# MAIN.net
KiCad netlist of a schematic drawn in Altium Designer
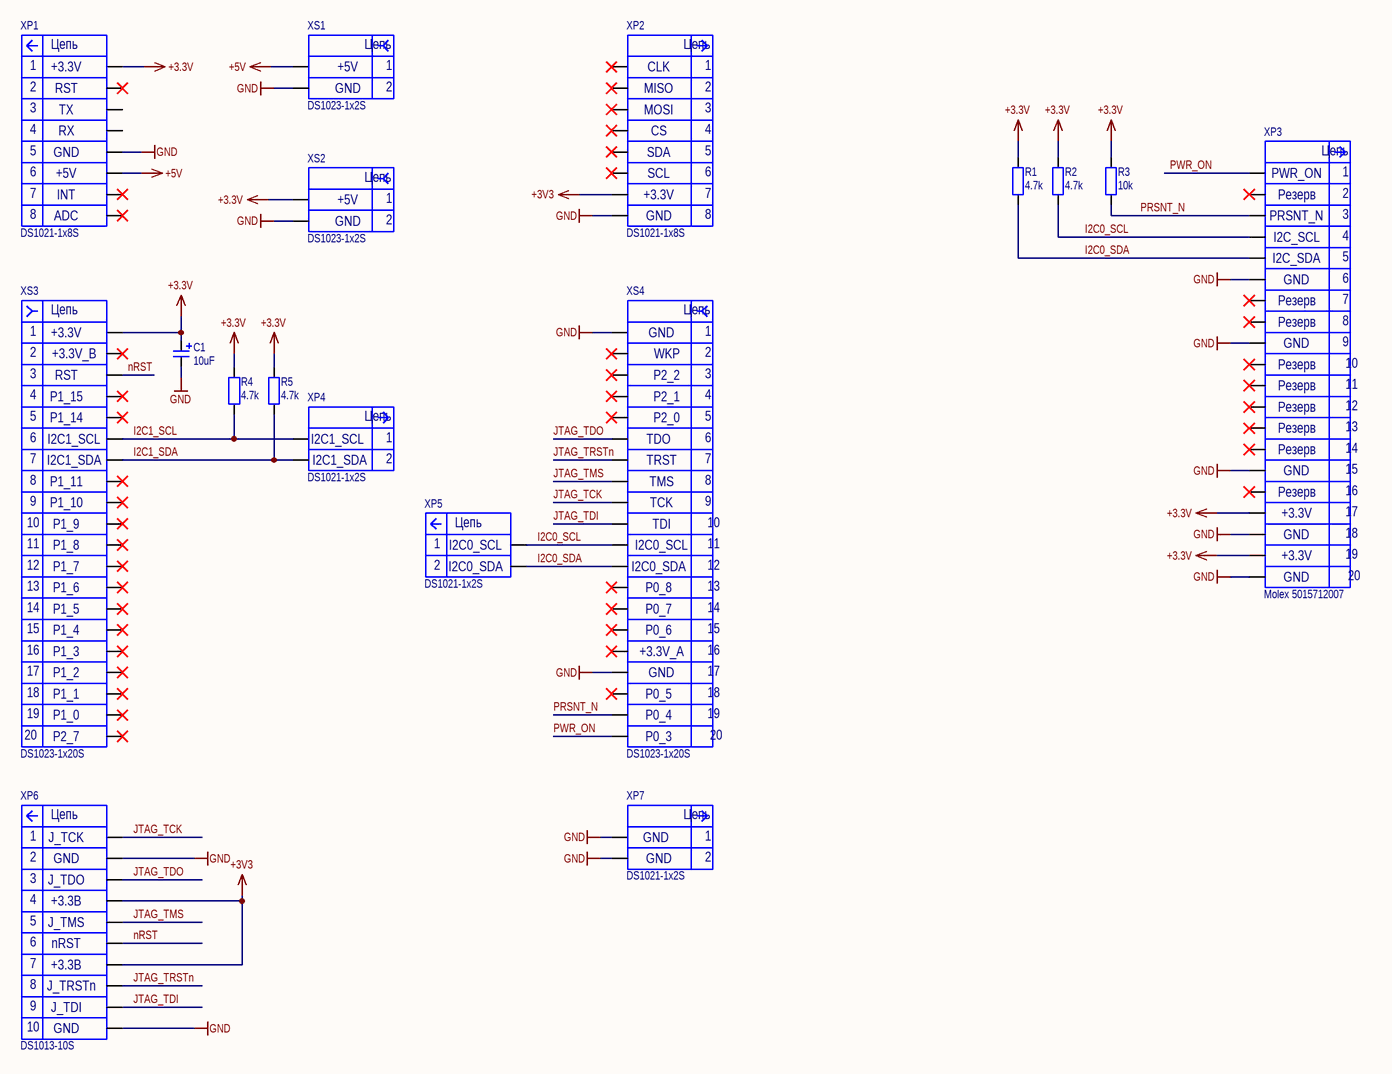
[diagram p0: MAIN.SchDoc]

(export (version "E")
  (design (tool "Eeschema 10.0.6"))
  (components
    (comp (ref "C1")
      (value "10uF")
      (footprint "CAP ALSMD ELEC 4.3MM H5.4MM")
      (description "Конденсатор К50-97 – 25В – 10мкФ (±20) % – ЕВАЯ.673541.054ТУ")
      (fields
        (field (name "MANUFACTURER PART NUMBER") "К50-97 – 25В – 10мкФ (±20) % – ЕВАЯ.673541.054ТУ")
        (field (name "TOLERANCE") "± 20%")
      )
      (libsource (lib "ComponentsDb") (part "Capacitor_Polar"))
    )
    (comp (ref "R1")
      (value "4.7k")
      (footprint "RES 0603_1608")
      (description "Резистор 0603-0,1Вт-4.7кОм ± 1%")
      (fields (field (name "MANUFACTURER PART NUMBER") "RC0603FR-074K7L") (field (name "TOLERANCE") "± 1%"))
      (libsource (lib "ComponentsDb") (part "Resistor_b"))
    )
    (comp (ref "R2")
      (value "4.7k")
      (footprint "RES 0603_1608")
      (description "Резистор 0603-0,1Вт-4.7кОм ± 1%")
      (fields (field (name "MANUFACTURER PART NUMBER") "RC0603FR-074K7L") (field (name "TOLERANCE") "± 1%"))
      (libsource (lib "ComponentsDb") (part "Resistor_b"))
    )
    (comp (ref "R3")
      (value "10k")
      (footprint "RES 0603_1608")
      (description "Резистор 0603-0,1Вт-10кОм ± 1%")
      (fields (field (name "MANUFACTURER PART NUMBER") "RC0603FR-0710KL") (field (name "TOLERANCE") "± 1%"))
      (libsource (lib "ComponentsDb") (part "Resistor_b"))
    )
    (comp (ref "R4")
      (value "4.7k")
      (footprint "RES 0603_1608")
      (description "Резистор 0603-0,1Вт-4.7кОм ± 1%")
      (fields (field (name "MANUFACTURER PART NUMBER") "RC0603FR-074K7L") (field (name "TOLERANCE") "± 1%"))
      (libsource (lib "ComponentsDb") (part "Resistor_b"))
    )
    (comp (ref "R5")
      (value "4.7k")
      (footprint "RES 0603_1608")
      (description "Резистор 0603-0,1Вт-4.7кОм ± 1%")
      (fields (field (name "MANUFACTURER PART NUMBER") "RC0603FR-074K7L") (field (name "TOLERANCE") "± 1%"))
      (libsource (lib "ComponentsDb") (part "Resistor_b"))
    )
    (comp (ref "XP1")
      (value "DS1021-1x8S")
      (footprint "DS1021-1x8S")
      (description "Соединитель DS1021-1x8S")
      (fields
        (field (name "NET_8") "ADC")
        (field (name "NET_7") "INT")
        (field (name "NET_6") "+5V")
        (field (name "NET_5") "GND")
        (field (name "NET_4") "RX")
        (field (name "NET_3") "TX")
        (field (name "NET_2") "RST")
        (field (name "NET_1") "+3.3V")
        (field (name "MANUFACTURER") "Connfly")
      )
      (libsource (lib "ComponentsDb") (part "Plug_8pin"))
    )
    (comp (ref "XP2")
      (value "DS1021-1x8S")
      (footprint "DS1021-1x8S")
      (description "Соединитель DS1021-1x8S")
      (fields
        (field (name "NET_8") "GND")
        (field (name "NET_7") "+3.3V")
        (field (name "NET_6") "SCL")
        (field (name "NET_5") "SDA")
        (field (name "NET_4") "CS")
        (field (name "NET_3") "MOSI")
        (field (name "NET_2") "MISO")
        (field (name "NET_1") "CLK")
        (field (name "MANUFACTURER") "Connfly")
      )
      (libsource (lib "ComponentsDb") (part "Plug_8pin"))
    )
    (comp (ref "XP3")
      (value "Molex 5015712007")
      (footprint "Molex 5015712007")
      (description "Соединитель Molex 5015712007")
      (fields
        (field (name "NET_20") "GND")
        (field (name "NET_19") "+3.3V")
        (field (name "NET_18") "GND")
        (field (name "NET_17") "+3.3V")
        (field (name "NET_16") "Резерв")
        (field (name "NET_15") "GND")
        (field (name "NET_14") "Резерв")
        (field (name "NET_13") "Резерв")
        (field (name "NET_12") "Резерв")
        (field (name "NET_11") "Резерв")
        (field (name "NET_10") "Резерв")
        (field (name "NET_9") "GND")
        (field (name "NET_8") "Резерв")
        (field (name "NET_7") "Резерв")
        (field (name "NET_6") "GND")
        (field (name "NET_5") "I2C_SDA")
        (field (name "NET_4") "I2C_SCL")
        (field (name "NET_3") "PRSNT_N")
        (field (name "NET_2") "Резерв")
        (field (name "NET_1") "PWR_ON")
        (field (name "MANUFACTURER") "Molex")
      )
      (libsource (lib "ComponentsDb") (part "Plug_20pin"))
    )
    (comp (ref "XP4")
      (value "DS1021-1x2S")
      (footprint "DS1021-1x2S")
      (description "Соединитель DS1021-1x2S")
      (fields
        (field (name "NET_2") "I2C1_SDA")
        (field (name "NET_1") "I2C1_SCL")
        (field (name "MANUFACTURER") "Connfly")
      )
      (libsource (lib "ComponentsDb") (part "Plug_2pin"))
    )
    (comp (ref "XP5")
      (value "DS1021-1x2S")
      (footprint "DS1021-1x2S")
      (description "Соединитель DS1021-1x2S")
      (fields
        (field (name "NET_2") "I2C0_SDA")
        (field (name "NET_1") "I2C0_SCL")
        (field (name "MANUFACTURER") "Connfly")
      )
      (libsource (lib "ComponentsDb") (part "Plug_2pin"))
    )
    (comp (ref "XP6")
      (value "DS1013-10S")
      (footprint "DS1013-10S")
      (description "Соединитель DS1013-10S")
      (fields
        (field (name "MANUFACTURER") "Connfly")
        (field (name "NET_10") "GND")
        (field (name "NET_9") "J_TDI")
        (field (name "NET_8") "J_TRSTn")
        (field (name "NET_7") "+3.3В")
        (field (name "NET_6") "nRST")
        (field (name "NET_5") "J_TMS")
        (field (name "NET_4") "+3.3В")
        (field (name "NET_3") "J_TDO")
        (field (name "NET_2") "GND")
        (field (name "NET_1") "J_TCK")
      )
      (libsource (lib "ComponentsDb") (part "Plug_10pin"))
    )
    (comp (ref "XP7")
      (value "DS1021-1x2S")
      (footprint "DS1021-1x2S")
      (description "Соединитель DS1021-1x2S")
      (fields
        (field (name "NET_2") "GND")
        (field (name "NET_1") "GND")
        (field (name "MANUFACTURER") "Connfly")
      )
      (libsource (lib "ComponentsDb") (part "Plug_2pin"))
    )
    (comp (ref "XS1")
      (value "DS1023-1x2S")
      (footprint "DS1023-1x2S")
      (description "Соединитель DS1023-1x2S")
      (fields
        (field (name "NET_2") "GND")
        (field (name "NET_1") "+5V")
        (field (name "MANUFACTURER") "Connfly")
      )
      (libsource (lib "ComponentsDb") (part "Socket_2pin"))
    )
    (comp (ref "XS2")
      (value "DS1023-1x2S")
      (footprint "DS1023-1x2S")
      (description "Соединитель DS1023-1x2S")
      (fields
        (field (name "NET_2") "GND")
        (field (name "NET_1") "+5V")
        (field (name "MANUFACTURER") "Connfly")
      )
      (libsource (lib "") (part "Socket_2pin_1"))
    )
    (comp (ref "XS3")
      (value "DS1023-1x20S")
      (footprint "DS1023-1x20S")
      (description "Соединитель DS1023-1x20S")
      (fields
        (field (name "NET_20") "P2_7")
        (field (name "NET_19") "P1_0")
        (field (name "NET_18") "P1_1")
        (field (name "NET_17") "P1_2")
        (field (name "NET_16") "P1_3")
        (field (name "NET_15") "P1_4")
        (field (name "NET_14") "P1_5")
        (field (name "NET_13") "P1_6")
        (field (name "NET_12") "P1_7")
        (field (name "NET_11") "P1_8")
        (field (name "NET_10") "P1_9")
        (field (name "NET_9") "P1_10")
        (field (name "NET_8") "P1_11")
        (field (name "NET_7") "I2C1_SDA")
        (field (name "NET_6") "I2C1_SCL")
        (field (name "NET_5") "P1_14")
        (field (name "NET_4") "P1_15")
        (field (name "NET_3") "RST")
        (field (name "NET_2") "+3.3V_B")
        (field (name "NET_1") "+3.3V")
        (field (name "MANUFACTURER") "Connfly")
      )
      (libsource (lib "ComponentsDb") (part "Socket_20pin"))
    )
    (comp (ref "XS4")
      (value "DS1023-1x20S")
      (footprint "DS1023-1x20S")
      (description "Соединитель DS1023-1x20S")
      (fields
        (field (name "NET_20") "P0_3")
        (field (name "NET_19") "P0_4")
        (field (name "NET_18") "P0_5")
        (field (name "NET_17") "GND")
        (field (name "NET_16") "+3.3V_A")
        (field (name "NET_15") "P0_6")
        (field (name "NET_14") "P0_7")
        (field (name "NET_13") "P0_8")
        (field (name "NET_12") "I2C0_SDA")
        (field (name "NET_11") "I2C0_SCL")
        (field (name "NET_10") "TDI")
        (field (name "NET_9") "TCK")
        (field (name "NET_8") "TMS")
        (field (name "NET_7") "TRST")
        (field (name "NET_6") "TDO")
        (field (name "NET_5") "P2_0")
        (field (name "NET_4") "P2_1")
        (field (name "NET_3") "P2_2")
        (field (name "NET_2") "WKP")
        (field (name "NET_1") "GND")
        (field (name "MANUFACTURER") "Connfly")
      )
      (libsource (lib "ComponentsDb") (part "Socket_20pin"))
    )
  )
  (nets
    (net (code "1") (name "+3.3V") (class "Default")
      (node (ref "C1") (pin "1") (pinfunction "P_1") (pintype "passive"))
      (node (ref "R1") (pin "2") (pinfunction "2_2") (pintype "passive"))
      (node (ref "R2") (pin "2") (pinfunction "2_2") (pintype "passive"))
      (node (ref "R3") (pin "2") (pinfunction "2_2") (pintype "passive"))
      (node (ref "R4") (pin "2") (pinfunction "2_2") (pintype "passive"))
      (node (ref "R5") (pin "2") (pinfunction "2_2") (pintype "passive"))
      (node (ref "XP1") (pin "1") (pinfunction "1_1") (pintype "passive"))
      (node (ref "XP3") (pin "17") (pinfunction "17_17") (pintype "passive"))
      (node (ref "XP3") (pin "19") (pinfunction "19_19") (pintype "passive"))
      (node (ref "XS2") (pin "1") (pinfunction "1_1") (pintype "passive"))
      (node (ref "XS3") (pin "1") (pinfunction "1_1") (pintype "passive"))
    )
    (net (code "2") (name "+3V3") (class "Default")
      (node (ref "XP2") (pin "7") (pinfunction "7_7") (pintype "passive"))
      (node (ref "XP6") (pin "4") (pinfunction "4_4") (pintype "passive"))
      (node (ref "XP6") (pin "7") (pinfunction "7_7") (pintype "passive"))
    )
    (net (code "3") (name "+5V") (class "Default")
      (node (ref "XP1") (pin "6") (pinfunction "6_6") (pintype "passive"))
      (node (ref "XS1") (pin "1") (pinfunction "1_1") (pintype "passive"))
    )
    (net (code "4") (name "/I2C0_SCL") (class "Default")
      (node (ref "R2") (pin "1") (pinfunction "1_1") (pintype "passive"))
      (node (ref "XP3") (pin "4") (pinfunction "4_4") (pintype "passive"))
      (node (ref "XP5") (pin "1") (pinfunction "1_1") (pintype "passive"))
      (node (ref "XS4") (pin "11") (pinfunction "11_11") (pintype "passive"))
    )
    (net (code "5") (name "/I2C0_SDA") (class "Default")
      (node (ref "R1") (pin "1") (pinfunction "1_1") (pintype "passive"))
      (node (ref "XP3") (pin "5") (pinfunction "5_5") (pintype "passive"))
      (node (ref "XP5") (pin "2") (pinfunction "2_2") (pintype "passive"))
      (node (ref "XS4") (pin "12") (pinfunction "12_12") (pintype "passive"))
    )
    (net (code "6") (name "/I2C1_SCL") (class "Default")
      (node (ref "R4") (pin "1") (pinfunction "1_1") (pintype "passive"))
      (node (ref "XP4") (pin "1") (pinfunction "1_1") (pintype "passive"))
      (node (ref "XS3") (pin "6") (pinfunction "6_6") (pintype "passive"))
    )
    (net (code "7") (name "/I2C1_SDA") (class "Default")
      (node (ref "R5") (pin "1") (pinfunction "1_1") (pintype "passive"))
      (node (ref "XP4") (pin "2") (pinfunction "2_2") (pintype "passive"))
      (node (ref "XS3") (pin "7") (pinfunction "7_7") (pintype "passive"))
    )
    (net (code "8") (name "/JTAG_TCK") (class "Default")
      (node (ref "XP6") (pin "1") (pinfunction "1_1") (pintype "passive"))
      (node (ref "XS4") (pin "9") (pinfunction "9_9") (pintype "passive"))
    )
    (net (code "9") (name "/JTAG_TDI") (class "Default")
      (node (ref "XP6") (pin "9") (pinfunction "9_9") (pintype "passive"))
      (node (ref "XS4") (pin "10") (pinfunction "10_10") (pintype "passive"))
    )
    (net (code "10") (name "/JTAG_TDO") (class "Default")
      (node (ref "XP6") (pin "3") (pinfunction "3_3") (pintype "passive"))
      (node (ref "XS4") (pin "6") (pinfunction "6_6") (pintype "passive"))
    )
    (net (code "11") (name "/JTAG_TMS") (class "Default")
      (node (ref "XP6") (pin "5") (pinfunction "5_5") (pintype "passive"))
      (node (ref "XS4") (pin "8") (pinfunction "8_8") (pintype "passive"))
    )
    (net (code "12") (name "/JTAG_TRSTn") (class "Default")
      (node (ref "XP6") (pin "8") (pinfunction "8_8") (pintype "passive"))
      (node (ref "XS4") (pin "7") (pinfunction "7_7") (pintype "passive"))
    )
    (net (code "13") (name "/PRSNT_N") (class "Default")
      (node (ref "R3") (pin "1") (pinfunction "1_1") (pintype "passive"))
      (node (ref "XP3") (pin "3") (pinfunction "3_3") (pintype "passive"))
      (node (ref "XS4") (pin "19") (pinfunction "19_19") (pintype "passive"))
    )
    (net (code "14") (name "/PWR_ON") (class "Default")
      (node (ref "XP3") (pin "1") (pinfunction "1_1") (pintype "passive"))
      (node (ref "XS4") (pin "20") (pinfunction "20_20") (pintype "passive"))
    )
    (net (code "15") (name "/nRST") (class "Default")
      (node (ref "XP6") (pin "6") (pinfunction "6_6") (pintype "passive"))
      (node (ref "XS3") (pin "3") (pinfunction "3_3") (pintype "passive"))
    )
    (net (code "16") (name "GND") (class "Default")
      (node (ref "C1") (pin "2") (pinfunction "N_2") (pintype "passive"))
      (node (ref "XP1") (pin "5") (pinfunction "5_5") (pintype "passive"))
      (node (ref "XP2") (pin "8") (pinfunction "8_8") (pintype "passive"))
      (node (ref "XP3") (pin "15") (pinfunction "15_15") (pintype "passive"))
      (node (ref "XP3") (pin "18") (pinfunction "18_18") (pintype "passive"))
      (node (ref "XP3") (pin "20") (pinfunction "20_20") (pintype "passive"))
      (node (ref "XP3") (pin "6") (pinfunction "6_6") (pintype "passive"))
      (node (ref "XP3") (pin "9") (pinfunction "9_9") (pintype "passive"))
      (node (ref "XP6") (pin "10") (pinfunction "10_10") (pintype "passive"))
      (node (ref "XP6") (pin "2") (pinfunction "2_2") (pintype "passive"))
      (node (ref "XP7") (pin "1") (pinfunction "1_1") (pintype "passive"))
      (node (ref "XP7") (pin "2") (pinfunction "2_2") (pintype "passive"))
      (node (ref "XS1") (pin "2") (pinfunction "2_2") (pintype "passive"))
      (node (ref "XS2") (pin "2") (pinfunction "2_2") (pintype "passive"))
      (node (ref "XS4") (pin "1") (pinfunction "1_1") (pintype "passive"))
      (node (ref "XS4") (pin "17") (pinfunction "17_17") (pintype "passive"))
    )
    (net (code "17") (name "unconnected-(XP1-Pad2)") (class "Default")
      (node (ref "XP1") (pin "2") (pinfunction "2_2") (pintype "passive+no_connect"))
    )
    (net (code "18") (name "unconnected-(XP1-Pad3)") (class "Default")
      (node (ref "XP1") (pin "3") (pinfunction "3_3") (pintype "passive"))
    )
    (net (code "19") (name "unconnected-(XP1-Pad4)") (class "Default")
      (node (ref "XP1") (pin "4") (pinfunction "4_4") (pintype "passive"))
    )
    (net (code "20") (name "unconnected-(XP1-Pad7)") (class "Default")
      (node (ref "XP1") (pin "7") (pinfunction "7_7") (pintype "passive+no_connect"))
    )
    (net (code "21") (name "unconnected-(XP1-Pad8)") (class "Default")
      (node (ref "XP1") (pin "8") (pinfunction "8_8") (pintype "passive+no_connect"))
    )
    (net (code "22") (name "unconnected-(XP2-Pad1)") (class "Default")
      (node (ref "XP2") (pin "1") (pinfunction "1_1") (pintype "passive+no_connect"))
    )
    (net (code "23") (name "unconnected-(XP2-Pad2)") (class "Default")
      (node (ref "XP2") (pin "2") (pinfunction "2_2") (pintype "passive+no_connect"))
    )
    (net (code "24") (name "unconnected-(XP2-Pad3)") (class "Default")
      (node (ref "XP2") (pin "3") (pinfunction "3_3") (pintype "passive+no_connect"))
    )
    (net (code "25") (name "unconnected-(XP2-Pad4)") (class "Default")
      (node (ref "XP2") (pin "4") (pinfunction "4_4") (pintype "passive+no_connect"))
    )
    (net (code "26") (name "unconnected-(XP2-Pad5)") (class "Default")
      (node (ref "XP2") (pin "5") (pinfunction "5_5") (pintype "passive+no_connect"))
    )
    (net (code "27") (name "unconnected-(XP2-Pad6)") (class "Default")
      (node (ref "XP2") (pin "6") (pinfunction "6_6") (pintype "passive+no_connect"))
    )
    (net (code "28") (name "unconnected-(XP3-Pad2)") (class "Default")
      (node (ref "XP3") (pin "2") (pinfunction "2_2") (pintype "passive+no_connect"))
    )
    (net (code "29") (name "unconnected-(XP3-Pad7)") (class "Default")
      (node (ref "XP3") (pin "7") (pinfunction "7_7") (pintype "passive+no_connect"))
    )
    (net (code "30") (name "unconnected-(XP3-Pad8)") (class "Default")
      (node (ref "XP3") (pin "8") (pinfunction "8_8") (pintype "passive+no_connect"))
    )
    (net (code "31") (name "unconnected-(XP3-Pad10)") (class "Default")
      (node (ref "XP3") (pin "10") (pinfunction "10_10") (pintype "passive+no_connect"))
    )
    (net (code "32") (name "unconnected-(XP3-Pad11)") (class "Default")
      (node (ref "XP3") (pin "11") (pinfunction "11_11") (pintype "passive+no_connect"))
    )
    (net (code "33") (name "unconnected-(XP3-Pad12)") (class "Default")
      (node (ref "XP3") (pin "12") (pinfunction "12_12") (pintype "passive+no_connect"))
    )
    (net (code "34") (name "unconnected-(XP3-Pad13)") (class "Default")
      (node (ref "XP3") (pin "13") (pinfunction "13_13") (pintype "passive+no_connect"))
    )
    (net (code "35") (name "unconnected-(XP3-Pad14)") (class "Default")
      (node (ref "XP3") (pin "14") (pinfunction "14_14") (pintype "passive+no_connect"))
    )
    (net (code "36") (name "unconnected-(XP3-Pad16)") (class "Default")
      (node (ref "XP3") (pin "16") (pinfunction "16_16") (pintype "passive+no_connect"))
    )
    (net (code "37") (name "unconnected-(XS3-Pad2)") (class "Default")
      (node (ref "XS3") (pin "2") (pinfunction "2_2") (pintype "passive+no_connect"))
    )
    (net (code "38") (name "unconnected-(XS3-Pad4)") (class "Default")
      (node (ref "XS3") (pin "4") (pinfunction "4_4") (pintype "passive+no_connect"))
    )
    (net (code "39") (name "unconnected-(XS3-Pad5)") (class "Default")
      (node (ref "XS3") (pin "5") (pinfunction "5_5") (pintype "passive+no_connect"))
    )
    (net (code "40") (name "unconnected-(XS3-Pad8)") (class "Default")
      (node (ref "XS3") (pin "8") (pinfunction "8_8") (pintype "passive+no_connect"))
    )
    (net (code "41") (name "unconnected-(XS3-Pad9)") (class "Default")
      (node (ref "XS3") (pin "9") (pinfunction "9_9") (pintype "passive+no_connect"))
    )
    (net (code "42") (name "unconnected-(XS3-Pad10)") (class "Default")
      (node (ref "XS3") (pin "10") (pinfunction "10_10") (pintype "passive+no_connect"))
    )
    (net (code "43") (name "unconnected-(XS3-Pad11)") (class "Default")
      (node (ref "XS3") (pin "11") (pinfunction "11_11") (pintype "passive+no_connect"))
    )
    (net (code "44") (name "unconnected-(XS3-Pad12)") (class "Default")
      (node (ref "XS3") (pin "12") (pinfunction "12_12") (pintype "passive+no_connect"))
    )
    (net (code "45") (name "unconnected-(XS3-Pad13)") (class "Default")
      (node (ref "XS3") (pin "13") (pinfunction "13_13") (pintype "passive+no_connect"))
    )
    (net (code "46") (name "unconnected-(XS3-Pad14)") (class "Default")
      (node (ref "XS3") (pin "14") (pinfunction "14_14") (pintype "passive+no_connect"))
    )
    (net (code "47") (name "unconnected-(XS3-Pad15)") (class "Default")
      (node (ref "XS3") (pin "15") (pinfunction "15_15") (pintype "passive+no_connect"))
    )
    (net (code "48") (name "unconnected-(XS3-Pad16)") (class "Default")
      (node (ref "XS3") (pin "16") (pinfunction "16_16") (pintype "passive+no_connect"))
    )
    (net (code "49") (name "unconnected-(XS3-Pad17)") (class "Default")
      (node (ref "XS3") (pin "17") (pinfunction "17_17") (pintype "passive+no_connect"))
    )
    (net (code "50") (name "unconnected-(XS3-Pad18)") (class "Default")
      (node (ref "XS3") (pin "18") (pinfunction "18_18") (pintype "passive+no_connect"))
    )
    (net (code "51") (name "unconnected-(XS3-Pad19)") (class "Default")
      (node (ref "XS3") (pin "19") (pinfunction "19_19") (pintype "passive+no_connect"))
    )
    (net (code "52") (name "unconnected-(XS3-Pad20)") (class "Default")
      (node (ref "XS3") (pin "20") (pinfunction "20_20") (pintype "passive+no_connect"))
    )
    (net (code "53") (name "unconnected-(XS4-Pad2)") (class "Default")
      (node (ref "XS4") (pin "2") (pinfunction "2_2") (pintype "passive+no_connect"))
    )
    (net (code "54") (name "unconnected-(XS4-Pad3)") (class "Default")
      (node (ref "XS4") (pin "3") (pinfunction "3_3") (pintype "passive+no_connect"))
    )
    (net (code "55") (name "unconnected-(XS4-Pad4)") (class "Default")
      (node (ref "XS4") (pin "4") (pinfunction "4_4") (pintype "passive+no_connect"))
    )
    (net (code "56") (name "unconnected-(XS4-Pad5)") (class "Default")
      (node (ref "XS4") (pin "5") (pinfunction "5_5") (pintype "passive+no_connect"))
    )
    (net (code "57") (name "unconnected-(XS4-Pad13)") (class "Default")
      (node (ref "XS4") (pin "13") (pinfunction "13_13") (pintype "passive+no_connect"))
    )
    (net (code "58") (name "unconnected-(XS4-Pad14)") (class "Default")
      (node (ref "XS4") (pin "14") (pinfunction "14_14") (pintype "passive+no_connect"))
    )
    (net (code "59") (name "unconnected-(XS4-Pad15)") (class "Default")
      (node (ref "XS4") (pin "15") (pinfunction "15_15") (pintype "passive+no_connect"))
    )
    (net (code "60") (name "unconnected-(XS4-Pad16)") (class "Default")
      (node (ref "XS4") (pin "16") (pinfunction "16_16") (pintype "passive+no_connect"))
    )
    (net (code "61") (name "unconnected-(XS4-Pad18)") (class "Default")
      (node (ref "XS4") (pin "18") (pinfunction "18_18") (pintype "passive+no_connect"))
    )
  )
)
